# Pin_Decoupling.net
KiCad netlist of a schematic drawn in Altium Designer
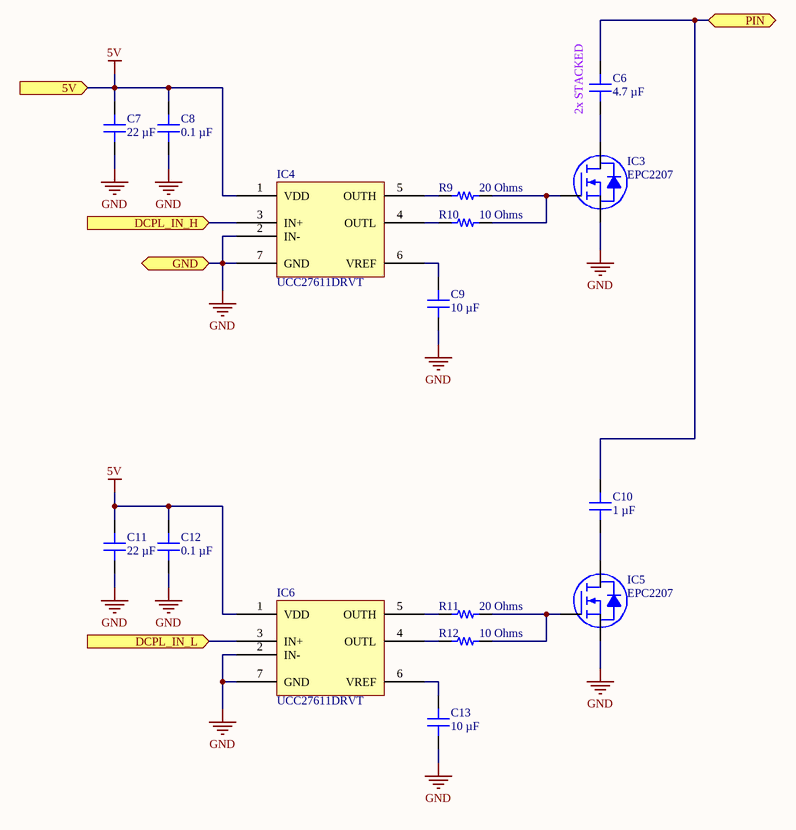
[diagram p0: Pin Decoupling.SchDoc]

(export (version "E")
  (design (tool "Eeschema 10.0.6"))
  (components
    (comp (ref "C6")
      (value "4.7 µF")
      (footprint "CAP 1206_3216 - 0.8MM")
      (description "CAP CER 4.7UF 100V X7R 1206")
      (fields
        (field (name "PART NUMBER") "GRJ31CZ72A475KE01L")
        (field (name "MANUFACTURER") "Murata Electronics")
      )
      (libsource (lib "altiumlibrary.com") (part "Capacitor"))
    )
    (comp (ref "C7")
      (value "22 µF")
      (footprint "CAP 0603_1608")
      (description "CAP CER 22UF 10V X5R 0603")
      (fields
        (field (name "PART NUMBER") "ZRB18AR61A226ME01L")
        (field (name "MANUFACTURER") "Murata Electronics")
      )
      (libsource (lib "altiumlibrary.com") (part "Capacitor"))
    )
    (comp (ref "C8")
      (value "0.1 µF")
      (footprint "CAP 0603_1608")
      (description "CAP CER 0.1UF 50V X7R 0603")
      (fields
        (field (name "PART NUMBER") "CL10B104KB8NNNC")
        (field (name "MANUFACTURER") "Samsung Electro-Mechanics")
      )
      (libsource (lib "altiumlibrary.com") (part "Capacitor"))
    )
    (comp (ref "C9")
      (value "10 µF")
      (footprint "CAP 0603_1608")
      (description "CAP CER 10UF 10V X5R 0603")
      (fields
        (field (name "PART NUMBER") "GRM188R61A106ME69J")
        (field (name "MANUFACTURER") "Murata Electronics")
      )
      (libsource (lib "altiumlibrary.com") (part "Capacitor"))
    )
    (comp (ref "C10")
      (value "1 µF")
      (footprint "CAP 1206_3216 - 0.8MM")
      (description "CAP CER 1UF 100V X7R 1206")
      (fields
        (field (name "PART NUMBER") "GCJ31CR72A105KA01L")
        (field (name "MANUFACTURER") "Murata Electronics")
      )
      (libsource (lib "altiumlibrary.com") (part "Capacitor"))
    )
    (comp (ref "C11")
      (value "22 µF")
      (footprint "CAP 0603_1608")
      (description "CAP CER 22UF 10V X5R 0603")
      (fields
        (field (name "PART NUMBER") "ZRB18AR61A226ME01L")
        (field (name "MANUFACTURER") "Murata Electronics")
      )
      (libsource (lib "altiumlibrary.com") (part "Capacitor"))
    )
    (comp (ref "C12")
      (value "0.1 µF")
      (footprint "CAP 0603_1608")
      (description "CAP CER 0.1UF 50V X7R 0603")
      (fields
        (field (name "PART NUMBER") "CL10B104KB8NNNC")
        (field (name "MANUFACTURER") "Samsung Electro-Mechanics")
      )
      (libsource (lib "altiumlibrary.com") (part "Capacitor"))
    )
    (comp (ref "C13")
      (value "10 µF")
      (footprint "CAP 0603_1608")
      (description "CAP CER 10UF 10V X5R 0603")
      (fields
        (field (name "PART NUMBER") "GRM188R61A106ME69J")
        (field (name "MANUFACTURER") "Murata Electronics")
      )
      (libsource (lib "altiumlibrary.com") (part "Capacitor"))
    )
    (comp (ref "IC3")
      (value "EPC2207")
      (footprint "EPC EPC2207")
      (description "TRANS GAN 200V DIE .022OHM")
      (fields (field (name "MANUFACTURER") "EPC"))
      (libsource (lib "altiumlibrary.com") (part "MOSFET SINGLE GDS"))
    )
    (comp (ref "IC4")
      (value "UCC27611DRVT")
      (footprint "TI WSON-6 DRV0006D 2x2MM")
      (description "IC GATE DRVR LOW-SIDE 6WSON")
      (fields (field (name "MANUFACTURER") "Texas Instruments"))
      (libsource (lib "altiumlibrary.com") (part "TI UCC27611"))
    )
    (comp (ref "IC5")
      (value "EPC2207")
      (footprint "EPC EPC2207")
      (description "TRANS GAN 200V DIE .022OHM")
      (fields (field (name "MANUFACTURER") "EPC"))
      (libsource (lib "altiumlibrary.com") (part "MOSFET SINGLE GDS"))
    )
    (comp (ref "IC6")
      (value "UCC27611DRVT")
      (footprint "TI WSON-6 DRV0006D 2x2MM")
      (description "IC GATE DRVR LOW-SIDE 6WSON")
      (fields (field (name "MANUFACTURER") "Texas Instruments"))
      (libsource (lib "altiumlibrary.com") (part "TI UCC27611"))
    )
    (comp (ref "R9")
      (value "20 Ohms")
      (footprint "RES 0603_1608")
      (description "RES SMD 20 OHM 1% 1/10W 0603")
      (fields
        (field (name "PART NUMBER") "ERJ-3EKF20R0V")
        (field (name "MANUFACTURER") "Panasonic Electronic Components")
      )
      (libsource (lib "altiumlibrary.com") (part "Resistor"))
    )
    (comp (ref "R10")
      (value "10 Ohms")
      (footprint "RES 0603_1608")
      (description "RES SMD 10 OHM 1% 1/10W 0603")
      (fields
        (field (name "PART NUMBER") "ERJ-3EKF10R0V")
        (field (name "MANUFACTURER") "Panasonic Electronic Components")
      )
      (libsource (lib "altiumlibrary.com") (part "Resistor"))
    )
    (comp (ref "R11")
      (value "20 Ohms")
      (footprint "RES 0603_1608")
      (description "RES SMD 20 OHM 1% 1/10W 0603")
      (fields
        (field (name "PART NUMBER") "ERJ-3EKF20R0V")
        (field (name "MANUFACTURER") "Panasonic Electronic Components")
      )
      (libsource (lib "altiumlibrary.com") (part "Resistor"))
    )
    (comp (ref "R12")
      (value "10 Ohms")
      (footprint "RES 0603_1608")
      (description "RES SMD 10 OHM 1% 1/10W 0603")
      (fields
        (field (name "PART NUMBER") "ERJ-3EKF10R0V")
        (field (name "MANUFACTURER") "Panasonic Electronic Components")
      )
      (libsource (lib "altiumlibrary.com") (part "Resistor"))
    )
  )
  (nets
    (net (code "1") (name "/DCPL_IN_H") (class "Default")
      (node (ref "IC4") (pin "3") (pinfunction "IN+_3") (pintype "passive"))
    )
    (net (code "2") (name "/DCPL_IN_L") (class "Default")
      (node (ref "IC6") (pin "3") (pinfunction "IN+_3") (pintype "passive"))
    )
    (net (code "3") (name "/PIN") (class "Default")
      (node (ref "C10") (pin "2") (pinfunction "2_2") (pintype "passive"))
      (node (ref "C6") (pin "2") (pinfunction "2_2") (pintype "passive"))
    )
    (net (code "4") (name "5V") (class "Default")
      (node (ref "C11") (pin "2") (pinfunction "2_2") (pintype "passive"))
      (node (ref "C12") (pin "2") (pinfunction "2_2") (pintype "passive"))
      (node (ref "C7") (pin "2") (pinfunction "2_2") (pintype "passive"))
      (node (ref "C8") (pin "2") (pinfunction "2_2") (pintype "passive"))
      (node (ref "IC4") (pin "1") (pinfunction "VDD_1") (pintype "passive"))
      (node (ref "IC6") (pin "1") (pinfunction "VDD_1") (pintype "passive"))
    )
    (net (code "5") (name "GND") (class "Default")
      (node (ref "C11") (pin "1") (pinfunction "1_1") (pintype "passive"))
      (node (ref "C12") (pin "1") (pinfunction "1_1") (pintype "passive"))
      (node (ref "C13") (pin "1") (pinfunction "1_1") (pintype "passive"))
      (node (ref "C7") (pin "1") (pinfunction "1_1") (pintype "passive"))
      (node (ref "C8") (pin "1") (pinfunction "1_1") (pintype "passive"))
      (node (ref "C9") (pin "1") (pinfunction "1_1") (pintype "passive"))
      (node (ref "IC3") (pin "S") (pinfunction "S_S") (pintype "passive"))
      (node (ref "IC4") (pin "2") (pinfunction "IN-_2") (pintype "passive"))
      (node (ref "IC4") (pin "7") (pinfunction "GND_7") (pintype "passive"))
      (node (ref "IC5") (pin "S") (pinfunction "S_S") (pintype "passive"))
      (node (ref "IC6") (pin "2") (pinfunction "IN-_2") (pintype "passive"))
      (node (ref "IC6") (pin "7") (pinfunction "GND_7") (pintype "passive"))
    )
    (net (code "6") (name "Net-(C6-Pad1)") (class "Default")
      (node (ref "C6") (pin "1") (pinfunction "1_1") (pintype "passive"))
      (node (ref "IC3") (pin "D") (pinfunction "D_D") (pintype "passive"))
    )
    (net (code "7") (name "Net-(C10-Pad1)") (class "Default")
      (node (ref "C10") (pin "1") (pinfunction "1_1") (pintype "passive"))
      (node (ref "IC5") (pin "D") (pinfunction "D_D") (pintype "passive"))
    )
    (net (code "8") (name "Net-(IC3-PadG)") (class "Default")
      (node (ref "IC3") (pin "G") (pinfunction "G_G") (pintype "passive"))
      (node (ref "R10") (pin "2") (pinfunction "2_2") (pintype "passive"))
      (node (ref "R9") (pin "2") (pinfunction "2_2") (pintype "passive"))
    )
    (net (code "9") (name "Net-(IC4-OUTH)") (class "Default")
      (node (ref "IC4") (pin "5") (pinfunction "OUTH_5") (pintype "passive"))
      (node (ref "R9") (pin "1") (pinfunction "1_1") (pintype "passive"))
    )
    (net (code "10") (name "Net-(IC4-OUTL)") (class "Default")
      (node (ref "IC4") (pin "4") (pinfunction "OUTL_4") (pintype "passive"))
      (node (ref "R10") (pin "1") (pinfunction "1_1") (pintype "passive"))
    )
    (net (code "11") (name "Net-(IC4-VREF)") (class "Default")
      (node (ref "C9") (pin "2") (pinfunction "2_2") (pintype "passive"))
      (node (ref "IC4") (pin "6") (pinfunction "VREF_6") (pintype "passive"))
    )
    (net (code "12") (name "Net-(IC5-PadG)") (class "Default")
      (node (ref "IC5") (pin "G") (pinfunction "G_G") (pintype "passive"))
      (node (ref "R11") (pin "2") (pinfunction "2_2") (pintype "passive"))
      (node (ref "R12") (pin "2") (pinfunction "2_2") (pintype "passive"))
    )
    (net (code "13") (name "Net-(IC6-OUTH)") (class "Default")
      (node (ref "IC6") (pin "5") (pinfunction "OUTH_5") (pintype "passive"))
      (node (ref "R11") (pin "1") (pinfunction "1_1") (pintype "passive"))
    )
    (net (code "14") (name "Net-(IC6-OUTL)") (class "Default")
      (node (ref "IC6") (pin "4") (pinfunction "OUTL_4") (pintype "passive"))
      (node (ref "R12") (pin "1") (pinfunction "1_1") (pintype "passive"))
    )
    (net (code "15") (name "Net-(IC6-VREF)") (class "Default")
      (node (ref "C13") (pin "2") (pinfunction "2_2") (pintype "passive"))
      (node (ref "IC6") (pin "6") (pinfunction "VREF_6") (pintype "passive"))
    )
  )
)
